# Connectors.net
KiCad netlist of a schematic drawn in Altium Designer
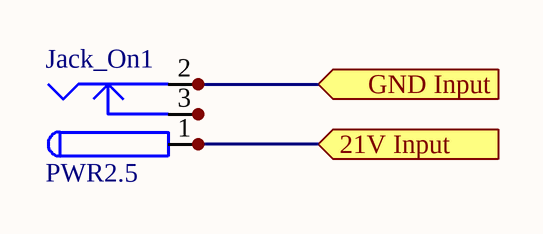
[diagram p0: Connectors.SchDoc]

(export (version "E")
  (design (tool "Eeschema 10.0.6"))
  (components
    (comp (ref "Jack_On1")
      (value "PWR2.5")
      (footprint "KLD-0202")
      (description "Low Voltage Power Supply Connector")
      (fields (field (name "PUBLISHER") "Altium Limited"))
      (libsource (lib "Miscellaneous Connectors") (part "PWR2.5"))
    )
  )
  (nets
    (net (code "1") (name "/21V Input") (class "Default")
      (node (ref "Jack_On1") (pin "1") (pinfunction "1_1") (pintype "power_in"))
      (node (ref "Jack_On1") (pin "1A") (pinfunction "1A_1A") (pintype "power_in"))
      (node (ref "Jack_On1") (pin "1B") (pinfunction "1B_1B") (pintype "power_in"))
    )
    (net (code "2") (name "/GND Input") (class "Default")
      (node (ref "Jack_On1") (pin "2") (pinfunction "2_2") (pintype "power_in"))
      (node (ref "Jack_On1") (pin "2A") (pinfunction "2A_2A") (pintype "power_in"))
      (node (ref "Jack_On1") (pin "2B") (pinfunction "2B_2B") (pintype "power_in"))
    )
    (net (code "3") (name "Net-(Jack_On1-Pad3)") (class "Default")
      (node (ref "Jack_On1") (pin "3") (pinfunction "3_3") (pintype "power_in"))
      (node (ref "Jack_On1") (pin "3A") (pinfunction "3A_3A") (pintype "power_in"))
      (node (ref "Jack_On1") (pin "3B") (pinfunction "3B_3B") (pintype "power_in"))
    )
  )
)
